# AmbaSat-07-CCS811.net
KiCad netlist of a schematic drawn in EAGLE
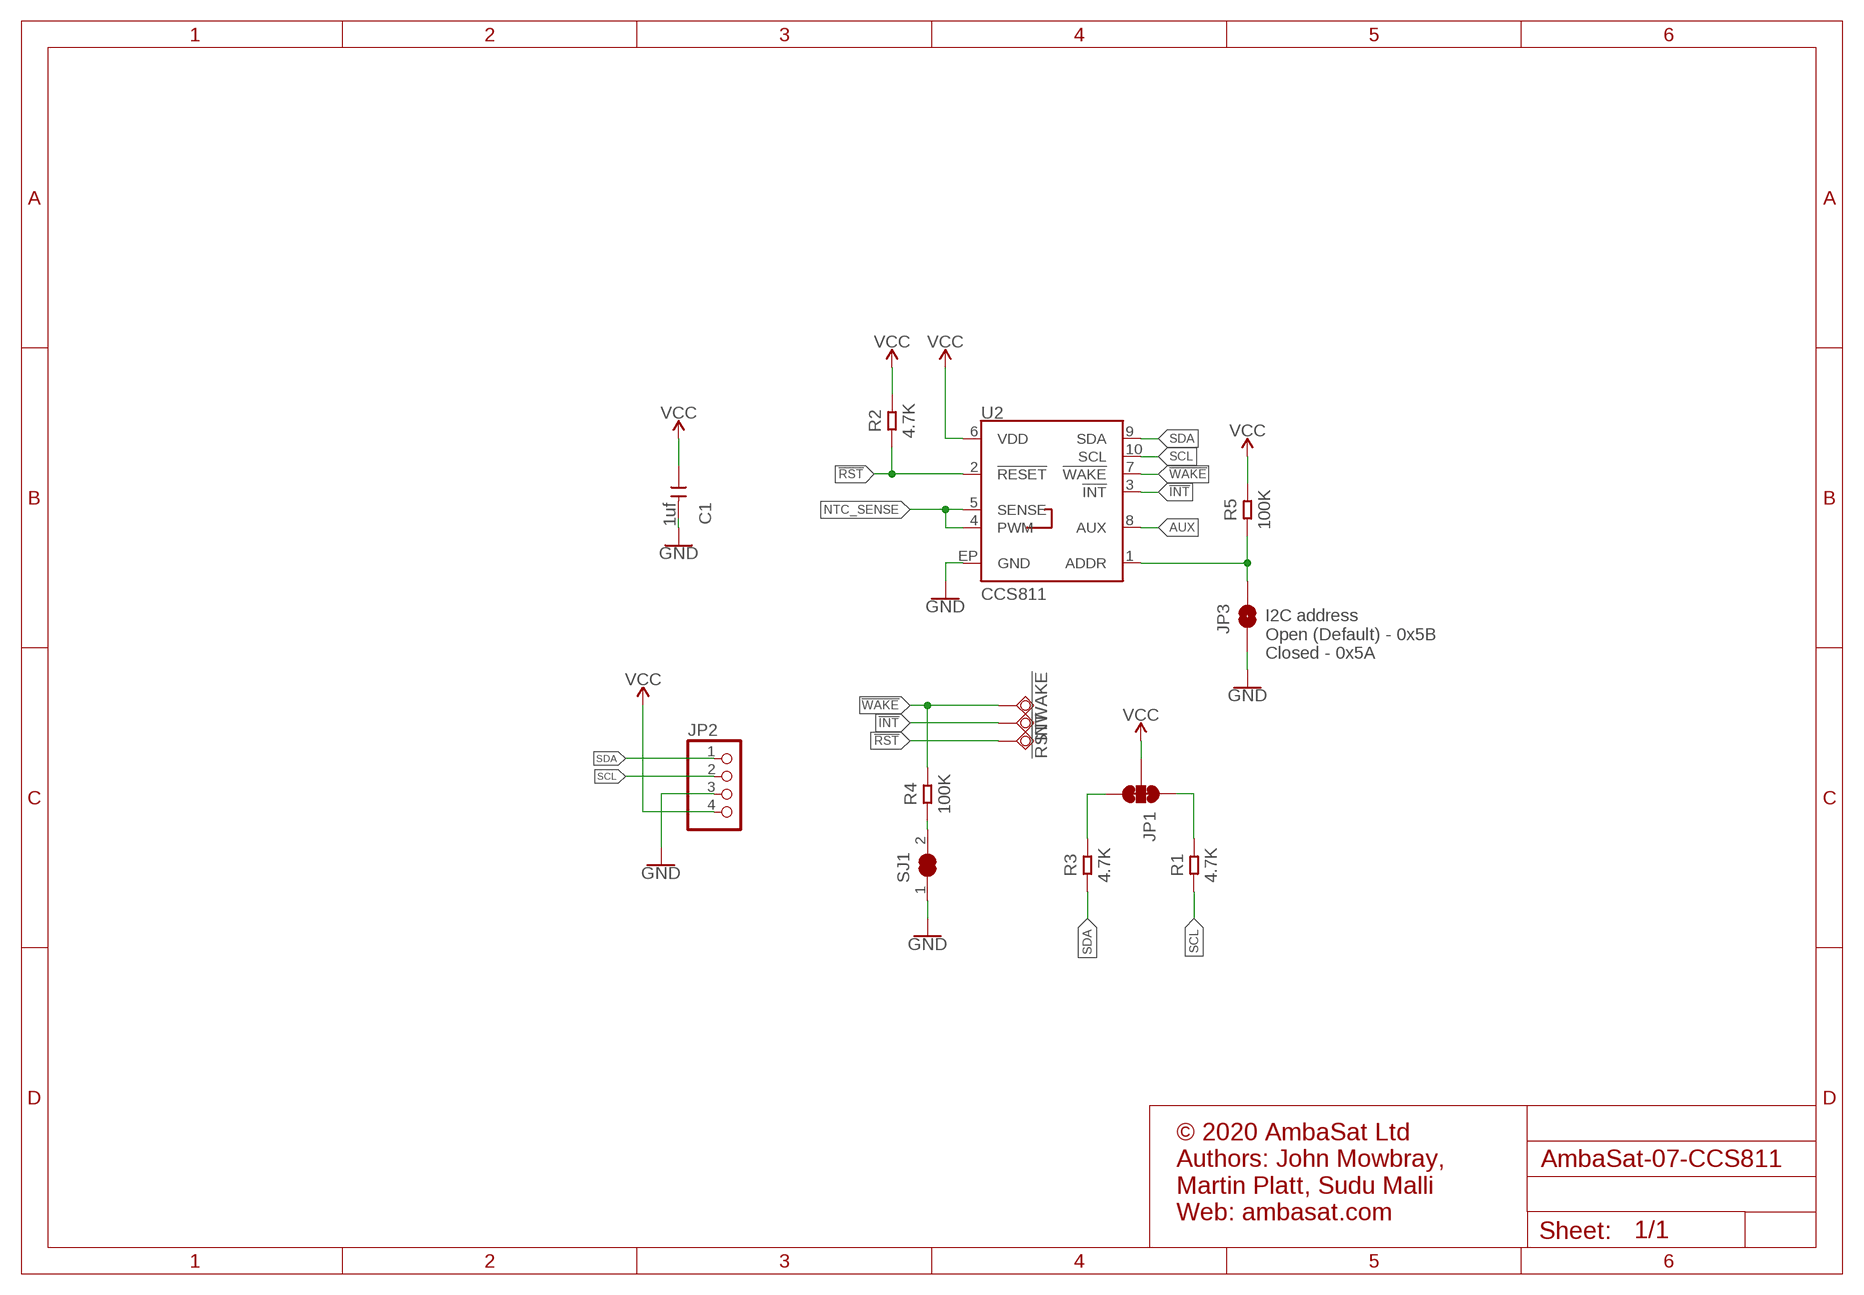
[diagram p0: schematic, sheet 1]

(export (version "E")
  (design (tool "Eeschema 10.0.6"))
  (components
    (comp (ref "!INT")
      (value "TESTPAD_TPSQTP14SQ")
      (footprint "eagle-import:TESTPAD_TP14SQ")
      (libsource (lib "eagle-import") (part "TESTPAD_TPSQTP14SQ"))
    )
    (comp (ref "!RST")
      (value "TESTPAD_TPSQTP14SQ")
      (footprint "eagle-import:TESTPAD_TP14SQ")
      (libsource (lib "eagle-import") (part "TESTPAD_TPSQTP14SQ"))
    )
    (comp (ref "!WAKE")
      (value "TESTPAD_TPSQTP14SQ")
      (footprint "eagle-import:TESTPAD_TP14SQ")
      (libsource (lib "eagle-import") (part "TESTPAD_TPSQTP14SQ"))
    )
    (comp (ref "C1")
      (value "1uf")
      (footprint "eagle-import:C0603")
      (fields (field (name "MPN") "CC0603KRX7R8BB105"))
      (libsource (lib "eagle-import") (part "CERAMIC-1UF-25V-10%-X7R(0603)"))
    )
    (comp (ref "JP1")
      (value "JUMPER-SMT_3_2-NC_TRACE_SILK")
      (footprint "eagle-import:SMT-JUMPER_3_2-NC_TRACE_SILK")
      (libsource (lib "eagle-import") (part "JUMPER-SMT_3_2-NC_TRACE_SILK"))
    )
    (comp (ref "JP2")
      (value "HEADER-1X4")
      (footprint "eagle-import:1X04_OVAL")
      (libsource (lib "eagle-import") (part "HEADER-1X4"))
    )
    (comp (ref "JP3")
      (value "JUMPER-SMT_2_NO_SILK")
      (footprint "eagle-import:SMT-JUMPER_2_NO_SILK")
      (libsource (lib "eagle-import") (part "JUMPER-SMT_2_NO_SILK"))
    )
    (comp (ref "R1")
      (value "4.7K")
      (footprint "eagle-import:R0603")
      (fields (field (name "MPN") "RC0603JR-074K7L"))
      (libsource (lib "eagle-import") (part "SMD-RES-4.7K-5%-1/10W(0603)"))
    )
    (comp (ref "R2")
      (value "4.7K")
      (footprint "eagle-import:R0603")
      (fields (field (name "MPN") "RC0603JR-074K7L"))
      (libsource (lib "eagle-import") (part "SMD-RES-4.7K-5%-1/10W(0603)"))
    )
    (comp (ref "R3")
      (value "4.7K")
      (footprint "eagle-import:R0603")
      (fields (field (name "MPN") "RC0603JR-074K7L"))
      (libsource (lib "eagle-import") (part "SMD-RES-4.7K-5%-1/10W(0603)"))
    )
    (comp (ref "R4")
      (value "100K")
      (footprint "eagle-import:R0603")
      (fields (field (name "MPN") "RC0603FR-07100KL"))
      (libsource (lib "eagle-import") (part "SMD-RES-100K-1%-1/10W(0603)"))
    )
    (comp (ref "R5")
      (value "100K")
      (footprint "eagle-import:R0603")
      (fields (field (name "MPN") "RC0603FR-07100KL"))
      (libsource (lib "eagle-import") (part "SMD-RES-100K-1%-1/10W(0603)"))
    )
    (comp (ref "SJ1")
      (value "SOLDERJUMPER_CLOSED")
      (footprint "eagle-import:SOLDERJUMPER_CLOSEDWIRE")
      (libsource (lib "eagle-import") (part "SOLDERJUMPER_CLOSED"))
    )
    (comp (ref "U2")
      (value "CCS811")
      (footprint "eagle-import:LGA10")
      (libsource (lib "eagle-import") (part "CCS811"))
    )
  )
  (nets
    (net (code "1") (name "/~{INT}") (class "Default")
      (node (ref "!INT") (pin "TP") (pinfunction "TP_TP") (pintype "input"))
      (node (ref "U2") (pin "3") (pinfunction "~{INT}_3") (pintype "bidirectional"))
    )
    (net (code "2") (name "/~{RST}") (class "Default")
      (node (ref "!RST") (pin "TP") (pinfunction "TP_TP") (pintype "input"))
      (node (ref "R2") (pin "1") (pinfunction "1_1") (pintype "passive"))
      (node (ref "U2") (pin "2") (pinfunction "~{RESET}_2") (pintype "bidirectional"))
    )
    (net (code "3") (name "/~{WAKE}") (class "Default")
      (node (ref "!WAKE") (pin "TP") (pinfunction "TP_TP") (pintype "input"))
      (node (ref "R4") (pin "2") (pinfunction "2_2") (pintype "passive"))
      (node (ref "U2") (pin "7") (pinfunction "~{WAKE}_7") (pintype "bidirectional"))
    )
    (net (code "4") (name "AUX") (class "Default")
      (node (ref "U2") (pin "8") (pinfunction "AUX_8") (pintype "bidirectional"))
    )
    (net (code "5") (name "GND") (class "Default")
      (node (ref "C1") (pin "2") (pinfunction "2_2") (pintype "passive"))
      (node (ref "JP2") (pin "3") (pinfunction "3_3") (pintype "passive"))
      (node (ref "JP3") (pin "1") (pinfunction "1_1") (pintype "passive"))
      (node (ref "SJ1") (pin "1") (pinfunction "1_1") (pintype "passive"))
      (node (ref "U2") (pin "EP") (pinfunction "GND_EP") (pintype "bidirectional"))
    )
    (net (code "6") (name "NTC_SENSE") (class "Default")
      (node (ref "U2") (pin "4") (pinfunction "PWM_4") (pintype "bidirectional"))
      (node (ref "U2") (pin "5") (pinfunction "SENSE_5") (pintype "bidirectional"))
    )
    (net (code "7") (name "Net-(JP1-Pad1)") (class "Default")
      (node (ref "JP1") (pin "1") (pinfunction "1_1") (pintype "passive"))
      (node (ref "R1") (pin "2") (pinfunction "2_2") (pintype "passive"))
    )
    (net (code "8") (name "Net-(JP1-Pad3)") (class "Default")
      (node (ref "JP1") (pin "3") (pinfunction "3_3") (pintype "passive"))
      (node (ref "R3") (pin "2") (pinfunction "2_2") (pintype "passive"))
    )
    (net (code "9") (name "Net-(R4-Pad1)") (class "Default")
      (node (ref "R4") (pin "1") (pinfunction "1_1") (pintype "passive"))
      (node (ref "SJ1") (pin "2") (pinfunction "2_2") (pintype "passive"))
    )
    (net (code "10") (name "Net-(U2-ADDR)") (class "Default")
      (node (ref "JP3") (pin "2") (pinfunction "2_2") (pintype "passive"))
      (node (ref "R5") (pin "1") (pinfunction "1_1") (pintype "passive"))
      (node (ref "U2") (pin "1") (pinfunction "ADDR_1") (pintype "bidirectional"))
    )
    (net (code "11") (name "SCL") (class "Default")
      (node (ref "JP2") (pin "2") (pinfunction "2_2") (pintype "passive"))
      (node (ref "R1") (pin "1") (pinfunction "1_1") (pintype "passive"))
      (node (ref "U2") (pin "10") (pinfunction "SCL_10") (pintype "bidirectional"))
    )
    (net (code "12") (name "SDA") (class "Default")
      (node (ref "JP2") (pin "1") (pinfunction "1_1") (pintype "passive"))
      (node (ref "R3") (pin "1") (pinfunction "1_1") (pintype "passive"))
      (node (ref "U2") (pin "9") (pinfunction "SDA_9") (pintype "bidirectional"))
    )
    (net (code "13") (name "VCC") (class "Default")
      (node (ref "C1") (pin "1") (pinfunction "1_1") (pintype "passive"))
      (node (ref "JP1") (pin "2") (pinfunction "2_2") (pintype "passive"))
      (node (ref "JP2") (pin "4") (pinfunction "4_4") (pintype "passive"))
      (node (ref "R2") (pin "2") (pinfunction "2_2") (pintype "passive"))
      (node (ref "R5") (pin "2") (pinfunction "2_2") (pintype "passive"))
      (node (ref "U2") (pin "6") (pinfunction "VDD_6") (pintype "bidirectional"))
    )
  )
)
